# V1_0.net
KiCad netlist of a schematic drawn in Altium Designer
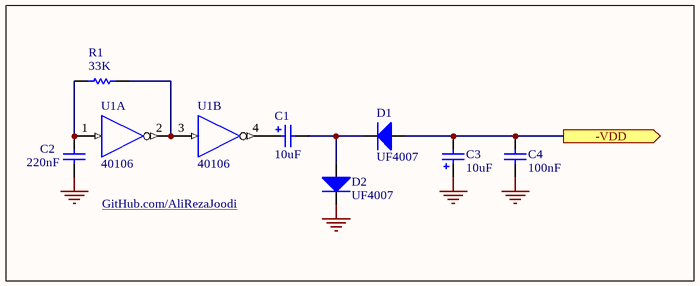
[diagram p0: V1.0.SchDoc]

(export (version "E")
  (design (tool "Eeschema 10.0.6"))
  (components
    (comp (ref "C1")
      (value "10uF")
      (footprint "CAPPR2.5-5x6")
      (description "Polarized Capacitor (Radial)")
      (fields (field (name "MANUFACTURER") "Generic Components") (field (name "PUBLISHER") "Altium Limited"))
      (libsource (lib "Miscellaneous Devices") (part "Cap Pol1"))
    )
    (comp (ref "C2")
      (value "220nF")
      (footprint "CAPNTO5.08-7.37x3.94")
      (description "Capacitor")
      (fields (field (name "PUBLISHER") "Altium Limited"))
      (libsource (lib "Miscellaneous Devices") (part "Cap"))
    )
    (comp (ref "C3")
      (value "10uF")
      (footprint "CAPPR2.5-5x6")
      (description "Polarized Capacitor (Radial)")
      (fields (field (name "MANUFACTURER") "Generic Components") (field (name "PUBLISHER") "Altium Limited"))
      (libsource (lib "Miscellaneous Devices") (part "Cap Pol1"))
    )
    (comp (ref "C4")
      (value "100nF")
      (footprint "CAPNTO2.54-3.05x1.78A")
      (description "Capacitor")
      (fields (field (name "MANUFACTURER") "Generic Components") (field (name "PUBLISHER") "Altium Limited"))
      (libsource (lib "Miscellaneous Devices") (part "Cap"))
    )
    (comp (ref "D1")
      (value "UF4007")
      (footprint "DIODE0.5_")
      (description "Default Diode")
      (fields (field (name "MANUFACTURER") "Generic Components") (field (name "PUBLISHER") "Altium Limited"))
      (libsource (lib "Miscellaneous Devices") (part "Diode"))
    )
    (comp (ref "D2")
      (value "UF4007")
      (footprint "DIODE0.5_")
      (description "Default Diode")
      (fields (field (name "MANUFACTURER") "Generic Components") (field (name "PUBLISHER") "Altium Limited"))
      (libsource (lib "Miscellaneous Devices") (part "Diode"))
    )
    (comp (ref "R1")
      (value "33K")
      (footprint "AXIAL-0.4")
      (description "Resistor")
      (fields (field (name "PUBLISHER") "Altium Limited"))
      (libsource (lib "Miscellaneous Devices") (part "Res1"))
    )
    (comp (ref "U1")
      (value "40106")
      (footprint "DIP14")
      (description "Hex inverting Schmitt trigger, 14-Pin")
      (fields (field (name "PUBLISHER") "Altium Limited"))
      (libsource (lib "my Libraries") (part "40106"))
    )
  )
  (nets
    (net (code "1") (name "/-VDD") (class "Default")
      (node (ref "C3") (pin "2") (pinfunction "2_2") (pintype "passive"))
      (node (ref "C4") (pin "2") (pinfunction "2_2") (pintype "passive"))
      (node (ref "D1") (pin "1") (pinfunction "A_1") (pintype "passive"))
    )
    (net (code "2") (name "GND") (class "Default")
      (node (ref "C2") (pin "1") (pinfunction "1_1") (pintype "passive"))
      (node (ref "C3") (pin "1") (pinfunction "1_1") (pintype "passive"))
      (node (ref "C4") (pin "1") (pinfunction "1_1") (pintype "passive"))
      (node (ref "D2") (pin "2") (pinfunction "K_2") (pintype "passive"))
    )
    (net (code "3") (name "Net-(D1-K)") (class "Default")
      (node (ref "C1") (pin "2") (pinfunction "2_2") (pintype "passive"))
      (node (ref "D1") (pin "2") (pinfunction "K_2") (pintype "passive"))
      (node (ref "D2") (pin "1") (pinfunction "A_1") (pintype "passive"))
    )
    (net (code "4") (name "Net-(U1A-I)") (class "Default")
      (node (ref "C2") (pin "2") (pinfunction "2_2") (pintype "passive"))
      (node (ref "R1") (pin "2") (pinfunction "2_2") (pintype "passive"))
      (node (ref "U1") (pin "1") (pinfunction "I_1") (pintype "input"))
    )
    (net (code "5") (name "Net-(U1A-~{O})") (class "Default")
      (node (ref "R1") (pin "1") (pinfunction "1_1") (pintype "passive"))
      (node (ref "U1") (pin "2") (pinfunction "~{O}_2") (pintype "output"))
      (node (ref "U1") (pin "3") (pinfunction "I_3") (pintype "input"))
    )
    (net (code "6") (name "Net-(U1B-~{O})") (class "Default")
      (node (ref "C1") (pin "1") (pinfunction "1_1") (pintype "passive"))
      (node (ref "U1") (pin "4") (pinfunction "~{O}_4") (pintype "output"))
    )
  )
)
